# CH340K6T-R0.net
KiCad netlist of a schematic drawn in Altium Designer
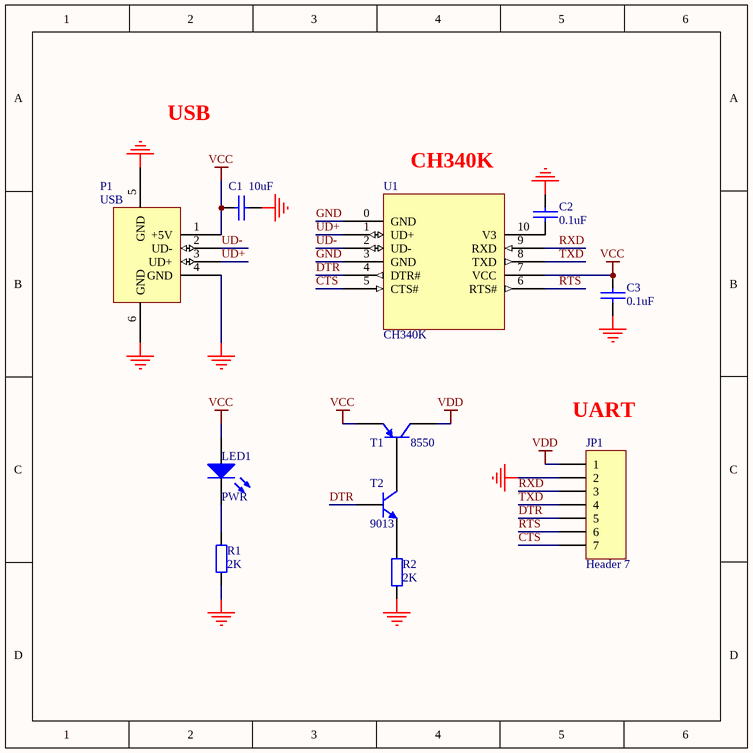
[diagram p0: CH340K6T-R0.SchDoc]

(export (version "E")
  (design (tool "Eeschema 10.0.6"))
  (components
    (comp (ref "C1")
      (value "10uF")
      (footprint "3216_C")
      (description "Capacitor")
      (libsource (lib "*") (part "CAP"))
    )
    (comp (ref "C2")
      (value "0.1uF")
      (footprint "0603_C")
      (description "Capacitor")
      (libsource (lib "*") (part "CAP"))
    )
    (comp (ref "C3")
      (value "0.1uF")
      (footprint "0603_C")
      (description "Capacitor")
      (libsource (lib "*") (part "CAP"))
    )
    (comp (ref "JP1")
      (value "Header 7")
      (footprint "SIP7-2.54mm")
      (description "Header, 7-Pin")
      (fields (field (name "PUBLISHER") "Altium Limited"))
      (libsource (lib "*") (part "Header 7"))
    )
    (comp (ref "LED1")
      (value "PWR")
      (footprint "0603+")
      (description "Typical RED, GREEN, YELLOW, AMBER GaAs LED")
      (libsource (lib "*") (part "LED2"))
    )
    (comp (ref "P1") (value "USB") (footprint "USBAM") (libsource (lib "*") (part "USB")))
    (comp (ref "R1")
      (value "2K")
      (footprint "0603")
      (description "Resistor")
      (libsource (lib "") (part "Res2_1"))
    )
    (comp (ref "R2")
      (value "2K")
      (footprint "0603")
      (description "Resistor")
      (libsource (lib "*") (part "Res2"))
    )
    (comp (ref "T1")
      (value "8550")
      (footprint "SOT-23")
      (description "PNP Bipolar Transistor")
      (libsource (lib "*") (part "PNP"))
    )
    (comp (ref "T2")
      (value "9013")
      (footprint "SOT-23")
      (description "NPN Bipolar Transistor")
      (libsource (lib "*") (part "NPN"))
    )
    (comp (ref "U1")
      (value "CH340K")
      (footprint "ESSOP10")
      (description "USB to TTL Serial / UART for dual power")
      (libsource (lib "*") (part "CH340K"))
    )
  )
  (nets
    (net (code "1") (name "/CTS") (class "Default")
      (node (ref "JP1") (pin "7") (pinfunction "7_7") (pintype "passive"))
      (node (ref "U1") (pin "5") (pinfunction "CTS#_5") (pintype "input"))
    )
    (net (code "2") (name "/DTR") (class "Default")
      (node (ref "JP1") (pin "5") (pinfunction "5_5") (pintype "passive"))
      (node (ref "T2") (pin "1") (pinfunction "B_1") (pintype "passive"))
      (node (ref "U1") (pin "4") (pinfunction "DTR#_4") (pintype "output"))
    )
    (net (code "3") (name "/RTS") (class "Default")
      (node (ref "JP1") (pin "6") (pinfunction "6_6") (pintype "passive"))
      (node (ref "U1") (pin "6") (pinfunction "RTS#_6") (pintype "output"))
    )
    (net (code "4") (name "/RXD") (class "Default")
      (node (ref "JP1") (pin "3") (pinfunction "3_3") (pintype "passive"))
      (node (ref "U1") (pin "9") (pinfunction "RXD_9") (pintype "input"))
    )
    (net (code "5") (name "/TXD") (class "Default")
      (node (ref "JP1") (pin "4") (pinfunction "4_4") (pintype "passive"))
      (node (ref "U1") (pin "8") (pinfunction "TXD_8") (pintype "output"))
    )
    (net (code "6") (name "/UD+") (class "Default")
      (node (ref "P1") (pin "3") (pinfunction "UD+_3") (pintype "bidirectional"))
      (node (ref "U1") (pin "1") (pinfunction "UD+_1") (pintype "bidirectional"))
    )
    (net (code "7") (name "/UD-") (class "Default")
      (node (ref "P1") (pin "2") (pinfunction "UD-_2") (pintype "bidirectional"))
      (node (ref "U1") (pin "2") (pinfunction "UD-_2") (pintype "bidirectional"))
    )
    (net (code "8") (name "GND") (class "Default")
      (node (ref "C1") (pin "2") (pinfunction "2_2") (pintype "passive"))
      (node (ref "C2") (pin "2") (pinfunction "2_2") (pintype "passive"))
      (node (ref "C3") (pin "1") (pinfunction "1_1") (pintype "passive"))
      (node (ref "JP1") (pin "2") (pinfunction "2_2") (pintype "passive"))
      (node (ref "P1") (pin "4") (pinfunction "GND_4") (pintype "power_in"))
      (node (ref "P1") (pin "5") (pinfunction "GND_5") (pintype "power_in"))
      (node (ref "P1") (pin "6") (pinfunction "GND_6") (pintype "power_in"))
      (node (ref "R1") (pin "2") (pinfunction "2_2") (pintype "passive"))
      (node (ref "R2") (pin "1") (pinfunction "1_1") (pintype "passive"))
      (node (ref "U1") (pin "0") (pinfunction "GND_0") (pintype "power_in"))
      (node (ref "U1") (pin "3") (pinfunction "GND_3") (pintype "power_in"))
    )
    (net (code "9") (name "Net-(LED1-K)") (class "Default")
      (node (ref "LED1") (pin "2") (pinfunction "K_2") (pintype "passive"))
      (node (ref "R1") (pin "1") (pinfunction "1_1") (pintype "passive"))
    )
    (net (code "10") (name "Net-(T1-B)") (class "Default")
      (node (ref "T1") (pin "1") (pinfunction "B_1") (pintype "passive"))
      (node (ref "T2") (pin "3") (pinfunction "C_3") (pintype "passive"))
    )
    (net (code "11") (name "Net-(T2-E)") (class "Default")
      (node (ref "R2") (pin "2") (pinfunction "2_2") (pintype "passive"))
      (node (ref "T2") (pin "2") (pinfunction "E_2") (pintype "passive"))
    )
    (net (code "12") (name "Net-(U1-V3)") (class "Default")
      (node (ref "C2") (pin "1") (pinfunction "1_1") (pintype "passive"))
      (node (ref "U1") (pin "10") (pinfunction "V3_10") (pintype "power_in"))
    )
    (net (code "13") (name "VCC") (class "Default")
      (node (ref "C1") (pin "1") (pinfunction "1_1") (pintype "passive"))
      (node (ref "C3") (pin "2") (pinfunction "2_2") (pintype "passive"))
      (node (ref "LED1") (pin "1") (pinfunction "A_1") (pintype "passive"))
      (node (ref "P1") (pin "1") (pinfunction "+5V_1") (pintype "power_in"))
      (node (ref "T1") (pin "2") (pinfunction "E_2") (pintype "passive"))
      (node (ref "U1") (pin "7") (pinfunction "VCC_7") (pintype "power_in"))
    )
    (net (code "14") (name "VDD") (class "Default")
      (node (ref "JP1") (pin "1") (pinfunction "1_1") (pintype "passive"))
      (node (ref "T1") (pin "3") (pinfunction "C_3") (pintype "passive"))
    )
  )
)
